# CAN_Belegtmelder.net
KiCad netlist of a schematic drawn in EAGLE
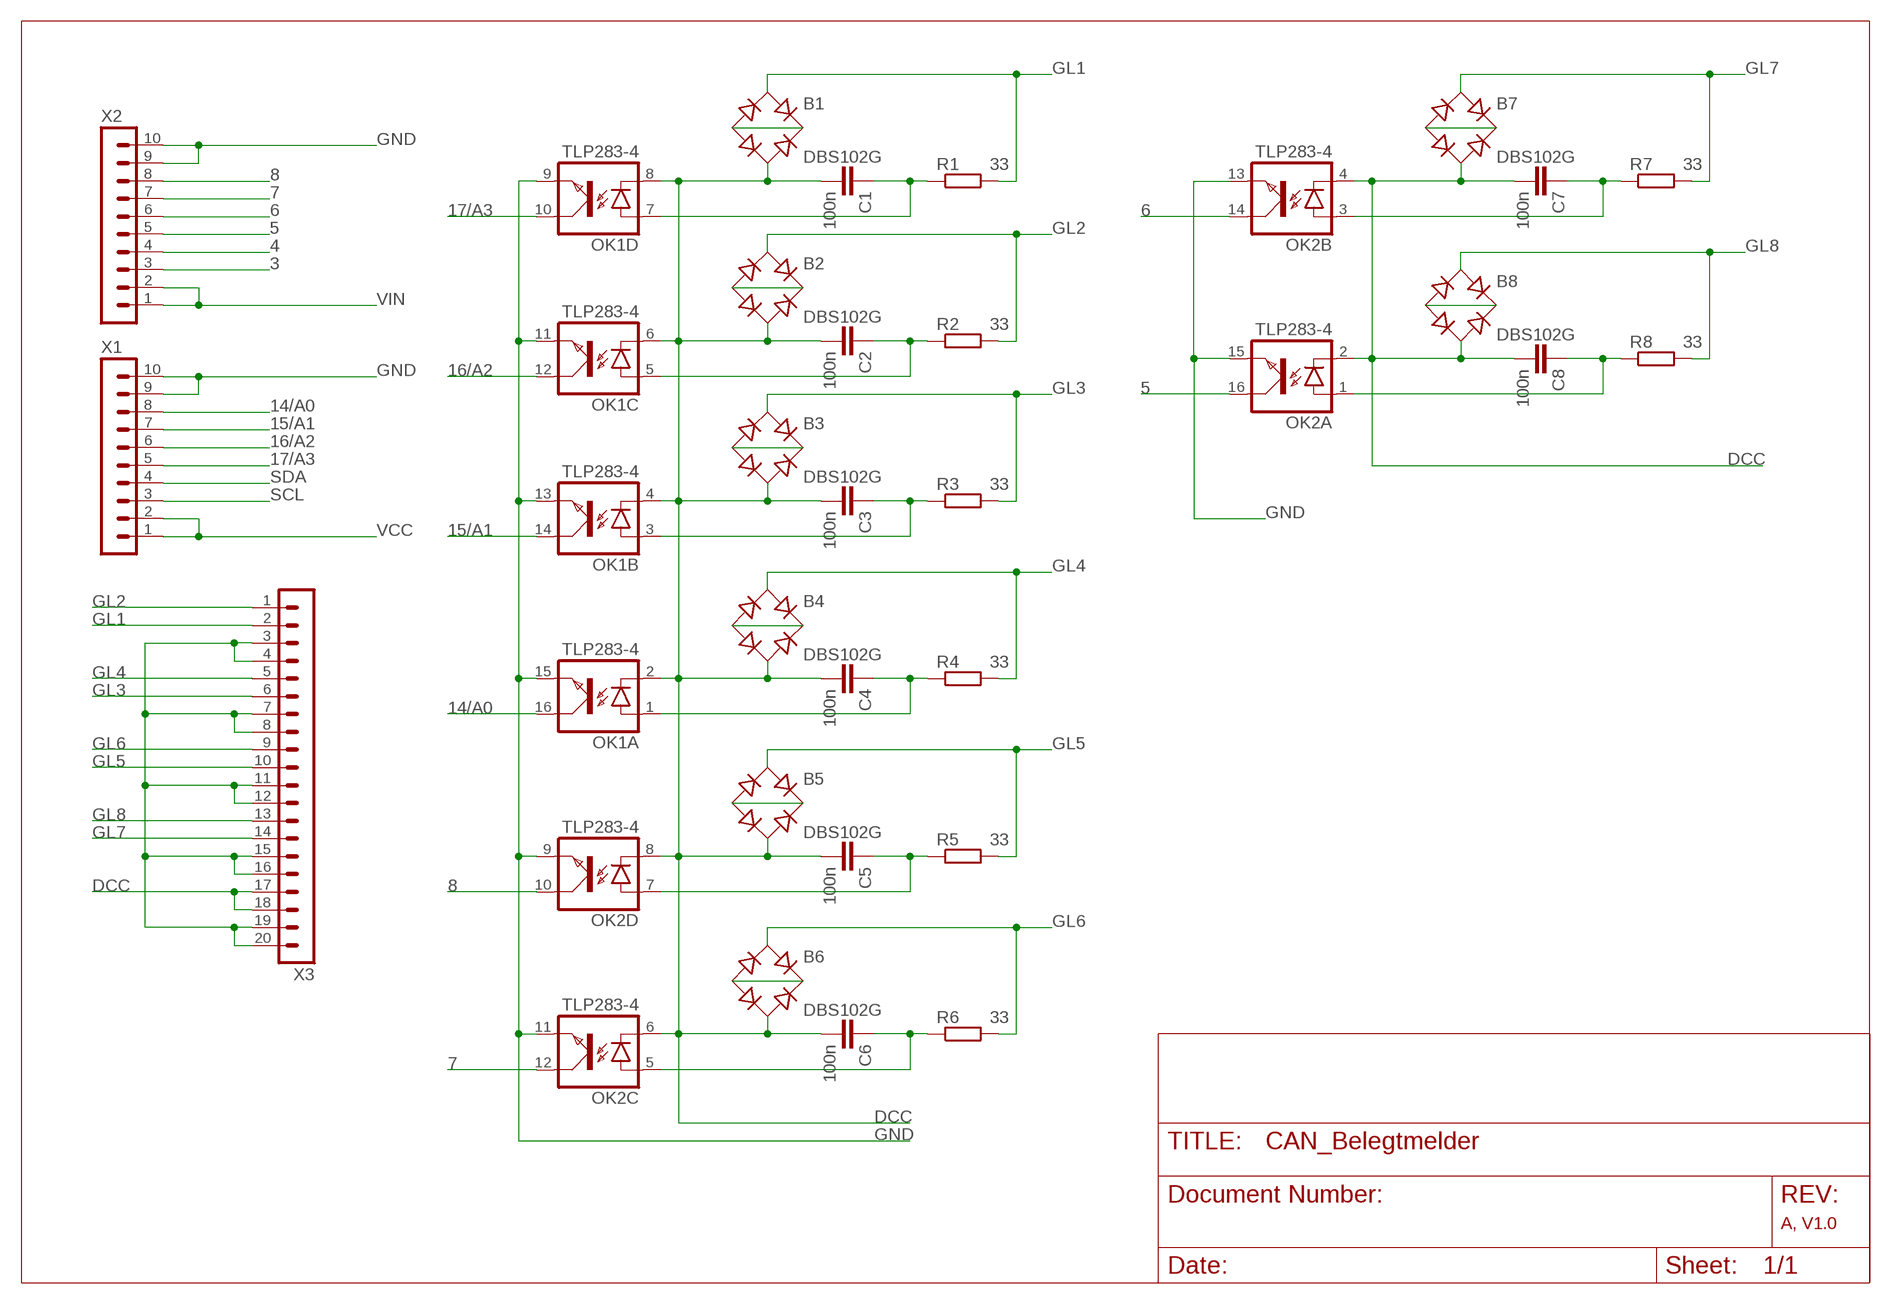
[diagram p0: schematic, sheet 1]

(export (version "E")
  (design (tool "Eeschema 10.0.6"))
  (components
    (comp (ref "B1")
      (value "DBS102G")
      (footprint "eagle-import:DBS")
      (libsource (lib "eagle-import") (part "DB?GS102"))
    )
    (comp (ref "B2")
      (value "DBS102G")
      (footprint "eagle-import:DBS")
      (libsource (lib "eagle-import") (part "DB?GS102"))
    )
    (comp (ref "B3")
      (value "DBS102G")
      (footprint "eagle-import:DBS")
      (libsource (lib "eagle-import") (part "DB?GS102"))
    )
    (comp (ref "B4")
      (value "DBS102G")
      (footprint "eagle-import:DBS")
      (libsource (lib "eagle-import") (part "DB?GS102"))
    )
    (comp (ref "B5")
      (value "DBS102G")
      (footprint "eagle-import:DBS")
      (libsource (lib "eagle-import") (part "DB?GS102"))
    )
    (comp (ref "B6")
      (value "DBS102G")
      (footprint "eagle-import:DBS")
      (libsource (lib "eagle-import") (part "DB?GS102"))
    )
    (comp (ref "B7")
      (value "DBS102G")
      (footprint "eagle-import:DBS")
      (libsource (lib "eagle-import") (part "DB?GS102"))
    )
    (comp (ref "B8")
      (value "DBS102G")
      (footprint "eagle-import:DBS")
      (libsource (lib "eagle-import") (part "DB?GS102"))
    )
    (comp (ref "C1")
      (value "100n")
      (footprint "eagle-import:C1206")
      (libsource (lib "eagle-import") (part "C-EUC1206"))
    )
    (comp (ref "C2")
      (value "100n")
      (footprint "eagle-import:C1206")
      (libsource (lib "eagle-import") (part "C-EUC1206"))
    )
    (comp (ref "C3")
      (value "100n")
      (footprint "eagle-import:C1206")
      (libsource (lib "eagle-import") (part "C-EUC1206"))
    )
    (comp (ref "C4")
      (value "100n")
      (footprint "eagle-import:C1206")
      (libsource (lib "eagle-import") (part "C-EUC1206"))
    )
    (comp (ref "C5")
      (value "100n")
      (footprint "eagle-import:C1206")
      (libsource (lib "eagle-import") (part "C-EUC1206"))
    )
    (comp (ref "C6")
      (value "100n")
      (footprint "eagle-import:C1206")
      (libsource (lib "eagle-import") (part "C-EUC1206"))
    )
    (comp (ref "C7")
      (value "100n")
      (footprint "eagle-import:C1206")
      (libsource (lib "eagle-import") (part "C-EUC1206"))
    )
    (comp (ref "C8")
      (value "100n")
      (footprint "eagle-import:C1206")
      (libsource (lib "eagle-import") (part "C-EUC1206"))
    )
    (comp (ref "OK1")
      (value "TLP283-4")
      (footprint "eagle-import:MINI-FLAT-16")
      (libsource (lib "eagle-import") (part "TLP283-4"))
    )
    (comp (ref "OK2")
      (value "TLP283-4")
      (footprint "eagle-import:MINI-FLAT-16")
      (libsource (lib "eagle-import") (part "TLP283-4"))
    )
    (comp (ref "R1")
      (value "33")
      (footprint "eagle-import:R1206")
      (libsource (lib "eagle-import") (part "R-EU_R1206"))
    )
    (comp (ref "R2")
      (value "33")
      (footprint "eagle-import:R1206")
      (libsource (lib "eagle-import") (part "R-EU_R1206"))
    )
    (comp (ref "R3")
      (value "33")
      (footprint "eagle-import:R1206")
      (libsource (lib "eagle-import") (part "R-EU_R1206"))
    )
    (comp (ref "R4")
      (value "33")
      (footprint "eagle-import:R1206")
      (libsource (lib "eagle-import") (part "R-EU_R1206"))
    )
    (comp (ref "R5")
      (value "33")
      (footprint "eagle-import:R1206")
      (libsource (lib "eagle-import") (part "R-EU_R1206"))
    )
    (comp (ref "R6")
      (value "33")
      (footprint "eagle-import:R1206")
      (libsource (lib "eagle-import") (part "R-EU_R1206"))
    )
    (comp (ref "R7")
      (value "33")
      (footprint "eagle-import:R1206")
      (libsource (lib "eagle-import") (part "R-EU_R1206"))
    )
    (comp (ref "R8")
      (value "33")
      (footprint "eagle-import:R1206")
      (libsource (lib "eagle-import") (part "R-EU_R1206"))
    )
    (comp (ref "X1")
      (value "MA10-1")
      (footprint "eagle-import:MA10-1")
      (libsource (lib "eagle-import") (part "MA10-1"))
    )
    (comp (ref "X2")
      (value "MA10-1")
      (footprint "eagle-import:MA10-1")
      (libsource (lib "eagle-import") (part "MA10-1"))
    )
    (comp (ref "X3")
      (value "MA20-1")
      (footprint "eagle-import:MA20-1")
      (libsource (lib "eagle-import") (part "MA20-1"))
    )
  )
  (nets
    (net (code "1") (name "/3") (class "Default")
      (node (ref "X2") (pin "3") (pinfunction "3_3") (pintype "passive"))
    )
    (net (code "2") (name "/4") (class "Default")
      (node (ref "X2") (pin "4") (pinfunction "4_4") (pintype "passive"))
    )
    (net (code "3") (name "/5") (class "Default")
      (node (ref "OK2") (pin "16") (pinfunction "COL_16") (pintype "passive"))
      (node (ref "X2") (pin "5") (pinfunction "5_5") (pintype "passive"))
    )
    (net (code "4") (name "/6") (class "Default")
      (node (ref "OK2") (pin "14") (pinfunction "COL_14") (pintype "passive"))
      (node (ref "X2") (pin "6") (pinfunction "6_6") (pintype "passive"))
    )
    (net (code "5") (name "/7") (class "Default")
      (node (ref "OK2") (pin "12") (pinfunction "COL_12") (pintype "passive"))
      (node (ref "X2") (pin "7") (pinfunction "7_7") (pintype "passive"))
    )
    (net (code "6") (name "/8") (class "Default")
      (node (ref "OK2") (pin "10") (pinfunction "COL_10") (pintype "passive"))
      (node (ref "X2") (pin "8") (pinfunction "8_8") (pintype "passive"))
    )
    (net (code "7") (name "/14{slash}A0") (class "Default")
      (node (ref "OK1") (pin "16") (pinfunction "COL_16") (pintype "passive"))
      (node (ref "X1") (pin "8") (pinfunction "8_8") (pintype "passive"))
    )
    (net (code "8") (name "/15{slash}A1") (class "Default")
      (node (ref "OK1") (pin "14") (pinfunction "COL_14") (pintype "passive"))
      (node (ref "X1") (pin "7") (pinfunction "7_7") (pintype "passive"))
    )
    (net (code "9") (name "/16{slash}A2") (class "Default")
      (node (ref "OK1") (pin "12") (pinfunction "COL_12") (pintype "passive"))
      (node (ref "X1") (pin "6") (pinfunction "6_6") (pintype "passive"))
    )
    (net (code "10") (name "/17{slash}A3") (class "Default")
      (node (ref "OK1") (pin "10") (pinfunction "COL_10") (pintype "passive"))
      (node (ref "X1") (pin "5") (pinfunction "5_5") (pintype "passive"))
    )
    (net (code "11") (name "/DCC") (class "Default")
      (node (ref "B1") (pin "AC2") (pinfunction "AC2_AC2") (pintype "passive"))
      (node (ref "B2") (pin "AC2") (pinfunction "AC2_AC2") (pintype "passive"))
      (node (ref "B3") (pin "AC2") (pinfunction "AC2_AC2") (pintype "passive"))
      (node (ref "B4") (pin "AC2") (pinfunction "AC2_AC2") (pintype "passive"))
      (node (ref "B5") (pin "AC2") (pinfunction "AC2_AC2") (pintype "passive"))
      (node (ref "B6") (pin "AC2") (pinfunction "AC2_AC2") (pintype "passive"))
      (node (ref "B7") (pin "AC2") (pinfunction "AC2_AC2") (pintype "passive"))
      (node (ref "B8") (pin "AC2") (pinfunction "AC2_AC2") (pintype "passive"))
      (node (ref "C1") (pin "2") (pinfunction "2_2") (pintype "passive"))
      (node (ref "C2") (pin "2") (pinfunction "2_2") (pintype "passive"))
      (node (ref "C3") (pin "2") (pinfunction "2_2") (pintype "passive"))
      (node (ref "C4") (pin "2") (pinfunction "2_2") (pintype "passive"))
      (node (ref "C5") (pin "2") (pinfunction "2_2") (pintype "passive"))
      (node (ref "C6") (pin "2") (pinfunction "2_2") (pintype "passive"))
      (node (ref "C7") (pin "2") (pinfunction "2_2") (pintype "passive"))
      (node (ref "C8") (pin "2") (pinfunction "2_2") (pintype "passive"))
      (node (ref "OK1") (pin "2") (pinfunction "C_2") (pintype "passive"))
      (node (ref "OK1") (pin "4") (pinfunction "C_4") (pintype "passive"))
      (node (ref "OK1") (pin "6") (pinfunction "C_6") (pintype "passive"))
      (node (ref "OK1") (pin "8") (pinfunction "C_8") (pintype "passive"))
      (node (ref "OK2") (pin "2") (pinfunction "C_2") (pintype "passive"))
      (node (ref "OK2") (pin "4") (pinfunction "C_4") (pintype "passive"))
      (node (ref "OK2") (pin "6") (pinfunction "C_6") (pintype "passive"))
      (node (ref "OK2") (pin "8") (pinfunction "C_8") (pintype "passive"))
      (node (ref "X3") (pin "17") (pinfunction "17_17") (pintype "passive"))
      (node (ref "X3") (pin "18") (pinfunction "18_18") (pintype "passive"))
    )
    (net (code "12") (name "/GL1") (class "Default")
      (node (ref "B1") (pin "AC1") (pinfunction "AC1_AC1") (pintype "passive"))
      (node (ref "R1") (pin "2") (pinfunction "2_2") (pintype "passive"))
      (node (ref "X3") (pin "2") (pinfunction "2_2") (pintype "passive"))
    )
    (net (code "13") (name "/GL2") (class "Default")
      (node (ref "B2") (pin "AC1") (pinfunction "AC1_AC1") (pintype "passive"))
      (node (ref "R2") (pin "2") (pinfunction "2_2") (pintype "passive"))
      (node (ref "X3") (pin "1") (pinfunction "1_1") (pintype "passive"))
    )
    (net (code "14") (name "/GL3") (class "Default")
      (node (ref "B3") (pin "AC1") (pinfunction "AC1_AC1") (pintype "passive"))
      (node (ref "R3") (pin "2") (pinfunction "2_2") (pintype "passive"))
      (node (ref "X3") (pin "6") (pinfunction "6_6") (pintype "passive"))
    )
    (net (code "15") (name "/GL4") (class "Default")
      (node (ref "B4") (pin "AC1") (pinfunction "AC1_AC1") (pintype "passive"))
      (node (ref "R4") (pin "2") (pinfunction "2_2") (pintype "passive"))
      (node (ref "X3") (pin "5") (pinfunction "5_5") (pintype "passive"))
    )
    (net (code "16") (name "/GL5") (class "Default")
      (node (ref "B5") (pin "AC1") (pinfunction "AC1_AC1") (pintype "passive"))
      (node (ref "R5") (pin "2") (pinfunction "2_2") (pintype "passive"))
      (node (ref "X3") (pin "10") (pinfunction "10_10") (pintype "passive"))
    )
    (net (code "17") (name "/GL6") (class "Default")
      (node (ref "B6") (pin "AC1") (pinfunction "AC1_AC1") (pintype "passive"))
      (node (ref "R6") (pin "2") (pinfunction "2_2") (pintype "passive"))
      (node (ref "X3") (pin "9") (pinfunction "9_9") (pintype "passive"))
    )
    (net (code "18") (name "/GL7") (class "Default")
      (node (ref "B7") (pin "AC1") (pinfunction "AC1_AC1") (pintype "passive"))
      (node (ref "R7") (pin "2") (pinfunction "2_2") (pintype "passive"))
      (node (ref "X3") (pin "14") (pinfunction "14_14") (pintype "passive"))
    )
    (net (code "19") (name "/GL8") (class "Default")
      (node (ref "B8") (pin "AC1") (pinfunction "AC1_AC1") (pintype "passive"))
      (node (ref "R8") (pin "2") (pinfunction "2_2") (pintype "passive"))
      (node (ref "X3") (pin "13") (pinfunction "13_13") (pintype "passive"))
    )
    (net (code "20") (name "/GND") (class "Default")
      (node (ref "OK1") (pin "11") (pinfunction "EMIT_11") (pintype "passive"))
      (node (ref "OK1") (pin "13") (pinfunction "EMIT_13") (pintype "passive"))
      (node (ref "OK1") (pin "15") (pinfunction "EMIT_15") (pintype "passive"))
      (node (ref "OK1") (pin "9") (pinfunction "EMIT_9") (pintype "passive"))
      (node (ref "OK2") (pin "11") (pinfunction "EMIT_11") (pintype "passive"))
      (node (ref "OK2") (pin "13") (pinfunction "EMIT_13") (pintype "passive"))
      (node (ref "OK2") (pin "15") (pinfunction "EMIT_15") (pintype "passive"))
      (node (ref "OK2") (pin "9") (pinfunction "EMIT_9") (pintype "passive"))
      (node (ref "X1") (pin "10") (pinfunction "10_10") (pintype "passive"))
      (node (ref "X1") (pin "9") (pinfunction "9_9") (pintype "passive"))
      (node (ref "X2") (pin "10") (pinfunction "10_10") (pintype "passive"))
      (node (ref "X2") (pin "9") (pinfunction "9_9") (pintype "passive"))
    )
    (net (code "21") (name "/SCL") (class "Default")
      (node (ref "X1") (pin "3") (pinfunction "3_3") (pintype "passive"))
    )
    (net (code "22") (name "/SDA") (class "Default")
      (node (ref "X1") (pin "4") (pinfunction "4_4") (pintype "passive"))
    )
    (net (code "23") (name "/VCC") (class "Default")
      (node (ref "X1") (pin "1") (pinfunction "1_1") (pintype "passive"))
      (node (ref "X1") (pin "2") (pinfunction "2_2") (pintype "passive"))
    )
    (net (code "24") (name "/VIN") (class "Default")
      (node (ref "X2") (pin "1") (pinfunction "1_1") (pintype "passive"))
      (node (ref "X2") (pin "2") (pinfunction "2_2") (pintype "passive"))
    )
    (net (code "25") (name "Net-(B1-Pad+)") (class "Default")
      (node (ref "B1") (pin "+") (pinfunction "+_+") (pintype "passive"))
      (node (ref "B1") (pin "-") (pinfunction "-_-") (pintype "passive"))
    )
    (net (code "26") (name "Net-(B2-Pad+)") (class "Default")
      (node (ref "B2") (pin "+") (pinfunction "+_+") (pintype "passive"))
      (node (ref "B2") (pin "-") (pinfunction "-_-") (pintype "passive"))
    )
    (net (code "27") (name "Net-(B3-Pad+)") (class "Default")
      (node (ref "B3") (pin "+") (pinfunction "+_+") (pintype "passive"))
      (node (ref "B3") (pin "-") (pinfunction "-_-") (pintype "passive"))
    )
    (net (code "28") (name "Net-(B4-Pad+)") (class "Default")
      (node (ref "B4") (pin "+") (pinfunction "+_+") (pintype "passive"))
      (node (ref "B4") (pin "-") (pinfunction "-_-") (pintype "passive"))
    )
    (net (code "29") (name "Net-(B5-Pad+)") (class "Default")
      (node (ref "B5") (pin "+") (pinfunction "+_+") (pintype "passive"))
      (node (ref "B5") (pin "-") (pinfunction "-_-") (pintype "passive"))
    )
    (net (code "30") (name "Net-(B6-Pad+)") (class "Default")
      (node (ref "B6") (pin "+") (pinfunction "+_+") (pintype "passive"))
      (node (ref "B6") (pin "-") (pinfunction "-_-") (pintype "passive"))
    )
    (net (code "31") (name "Net-(B7-Pad+)") (class "Default")
      (node (ref "B7") (pin "+") (pinfunction "+_+") (pintype "passive"))
      (node (ref "B7") (pin "-") (pinfunction "-_-") (pintype "passive"))
    )
    (net (code "32") (name "Net-(B8-Pad+)") (class "Default")
      (node (ref "B8") (pin "+") (pinfunction "+_+") (pintype "passive"))
      (node (ref "B8") (pin "-") (pinfunction "-_-") (pintype "passive"))
    )
    (net (code "33") (name "Net-(OK1A-A)") (class "Default")
      (node (ref "C4") (pin "1") (pinfunction "1_1") (pintype "passive"))
      (node (ref "OK1") (pin "1") (pinfunction "A_1") (pintype "passive"))
      (node (ref "R4") (pin "1") (pinfunction "1_1") (pintype "passive"))
    )
    (net (code "34") (name "Net-(OK1B-A)") (class "Default")
      (node (ref "C3") (pin "1") (pinfunction "1_1") (pintype "passive"))
      (node (ref "OK1") (pin "3") (pinfunction "A_3") (pintype "passive"))
      (node (ref "R3") (pin "1") (pinfunction "1_1") (pintype "passive"))
    )
    (net (code "35") (name "Net-(OK1C-A)") (class "Default")
      (node (ref "C2") (pin "1") (pinfunction "1_1") (pintype "passive"))
      (node (ref "OK1") (pin "5") (pinfunction "A_5") (pintype "passive"))
      (node (ref "R2") (pin "1") (pinfunction "1_1") (pintype "passive"))
    )
    (net (code "36") (name "Net-(OK1D-A)") (class "Default")
      (node (ref "C1") (pin "1") (pinfunction "1_1") (pintype "passive"))
      (node (ref "OK1") (pin "7") (pinfunction "A_7") (pintype "passive"))
      (node (ref "R1") (pin "1") (pinfunction "1_1") (pintype "passive"))
    )
    (net (code "37") (name "Net-(OK2A-A)") (class "Default")
      (node (ref "C8") (pin "1") (pinfunction "1_1") (pintype "passive"))
      (node (ref "OK2") (pin "1") (pinfunction "A_1") (pintype "passive"))
      (node (ref "R8") (pin "1") (pinfunction "1_1") (pintype "passive"))
    )
    (net (code "38") (name "Net-(OK2B-A)") (class "Default")
      (node (ref "C7") (pin "1") (pinfunction "1_1") (pintype "passive"))
      (node (ref "OK2") (pin "3") (pinfunction "A_3") (pintype "passive"))
      (node (ref "R7") (pin "1") (pinfunction "1_1") (pintype "passive"))
    )
    (net (code "39") (name "Net-(OK2C-A)") (class "Default")
      (node (ref "C6") (pin "1") (pinfunction "1_1") (pintype "passive"))
      (node (ref "OK2") (pin "5") (pinfunction "A_5") (pintype "passive"))
      (node (ref "R6") (pin "1") (pinfunction "1_1") (pintype "passive"))
    )
    (net (code "40") (name "Net-(OK2D-A)") (class "Default")
      (node (ref "C5") (pin "1") (pinfunction "1_1") (pintype "passive"))
      (node (ref "OK2") (pin "7") (pinfunction "A_7") (pintype "passive"))
      (node (ref "R5") (pin "1") (pinfunction "1_1") (pintype "passive"))
    )
    (net (code "41") (name "Net-(X3-Pad11)") (class "Default")
      (node (ref "X3") (pin "11") (pinfunction "11_11") (pintype "passive"))
      (node (ref "X3") (pin "12") (pinfunction "12_12") (pintype "passive"))
      (node (ref "X3") (pin "15") (pinfunction "15_15") (pintype "passive"))
      (node (ref "X3") (pin "16") (pinfunction "16_16") (pintype "passive"))
      (node (ref "X3") (pin "19") (pinfunction "19_19") (pintype "passive"))
      (node (ref "X3") (pin "20") (pinfunction "20_20") (pintype "passive"))
      (node (ref "X3") (pin "3") (pinfunction "3_3") (pintype "passive"))
      (node (ref "X3") (pin "4") (pinfunction "4_4") (pintype "passive"))
      (node (ref "X3") (pin "7") (pinfunction "7_7") (pintype "passive"))
      (node (ref "X3") (pin "8") (pinfunction "8_8") (pintype "passive"))
    )
  )
)
